# 4-voice_1_1.net
KiCad netlist of a schematic drawn in EAGLE
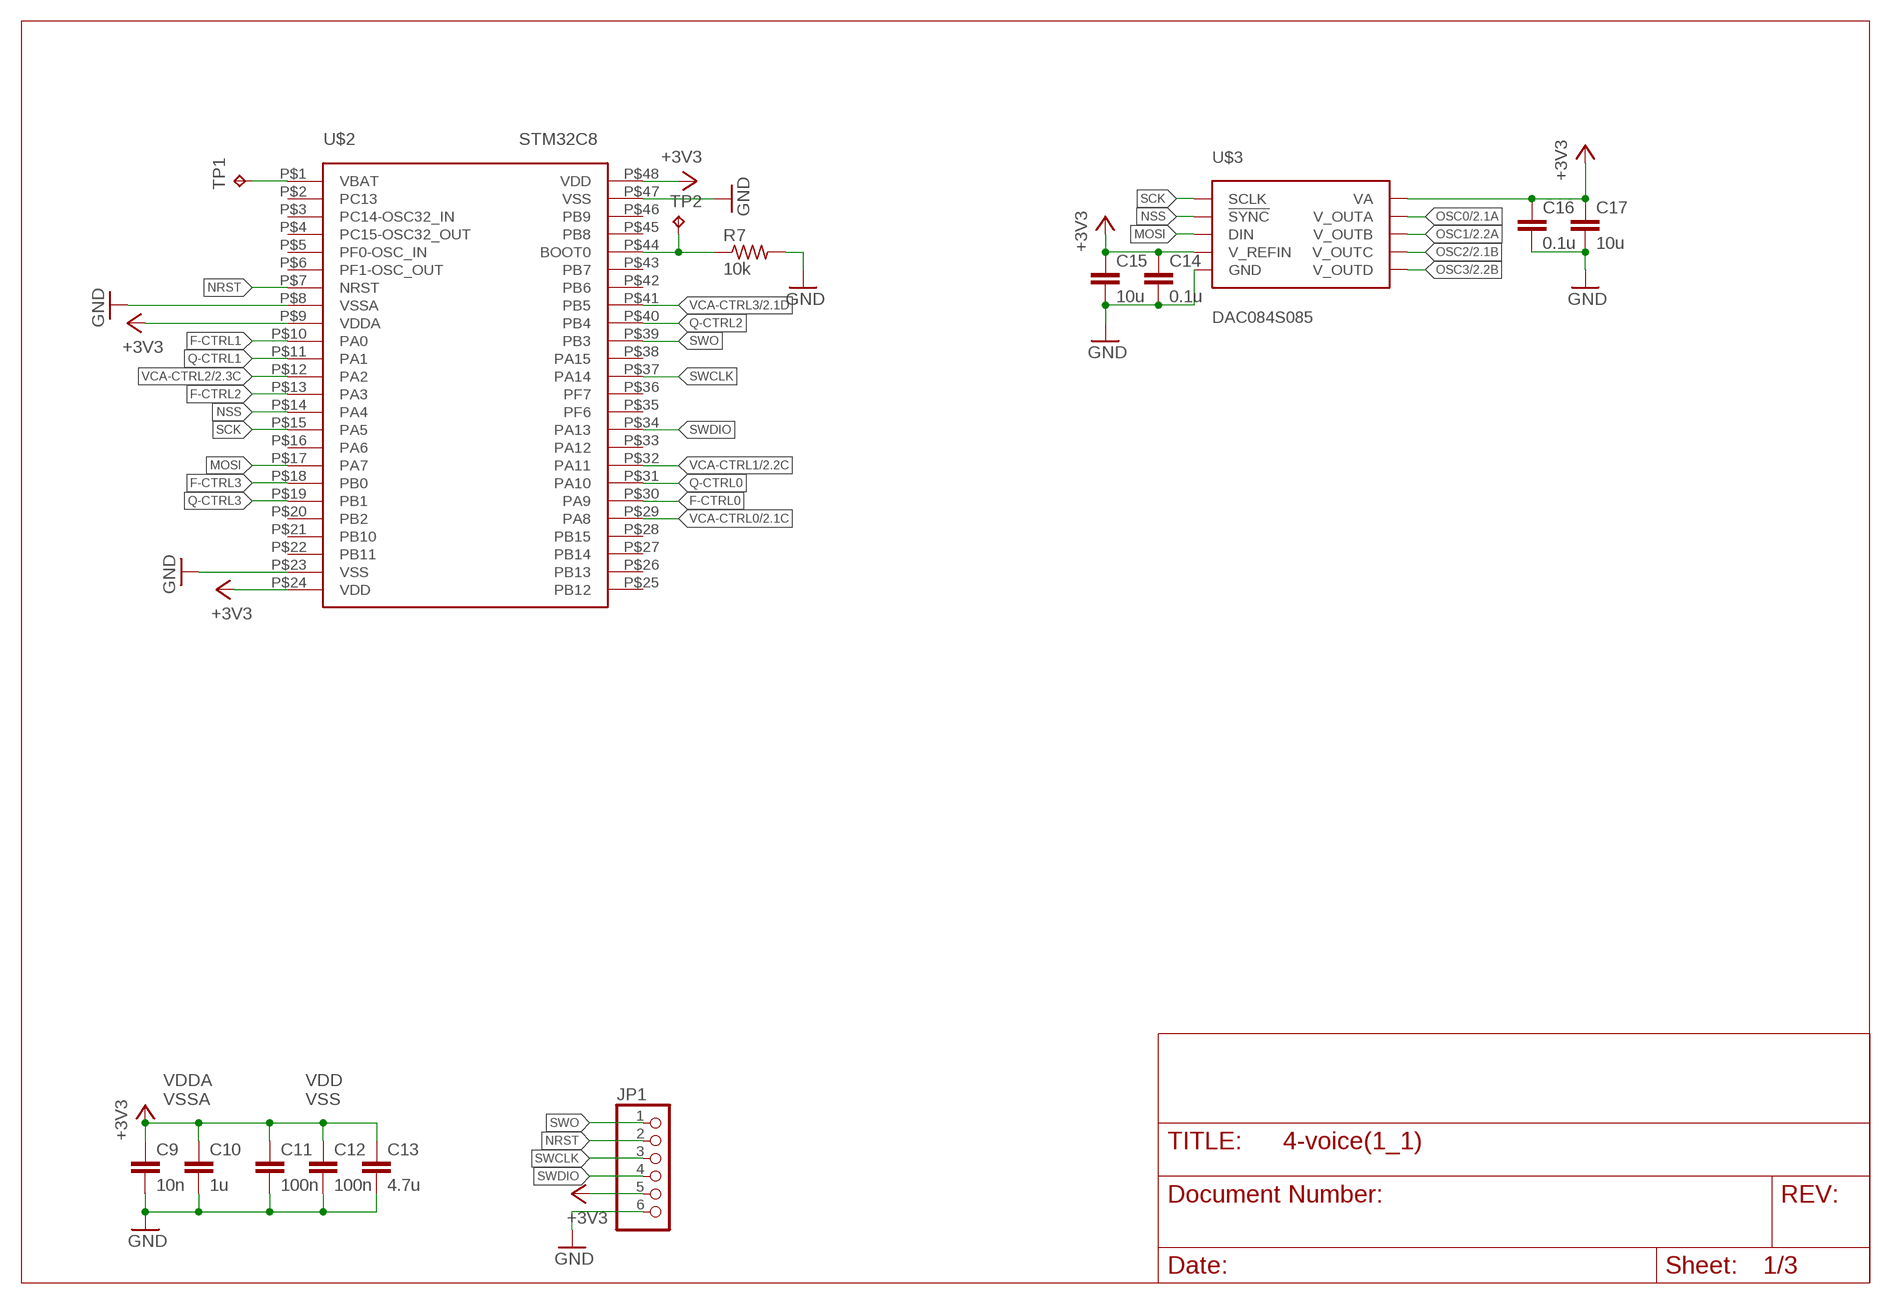
[diagram p0: schematic, sheet 1]
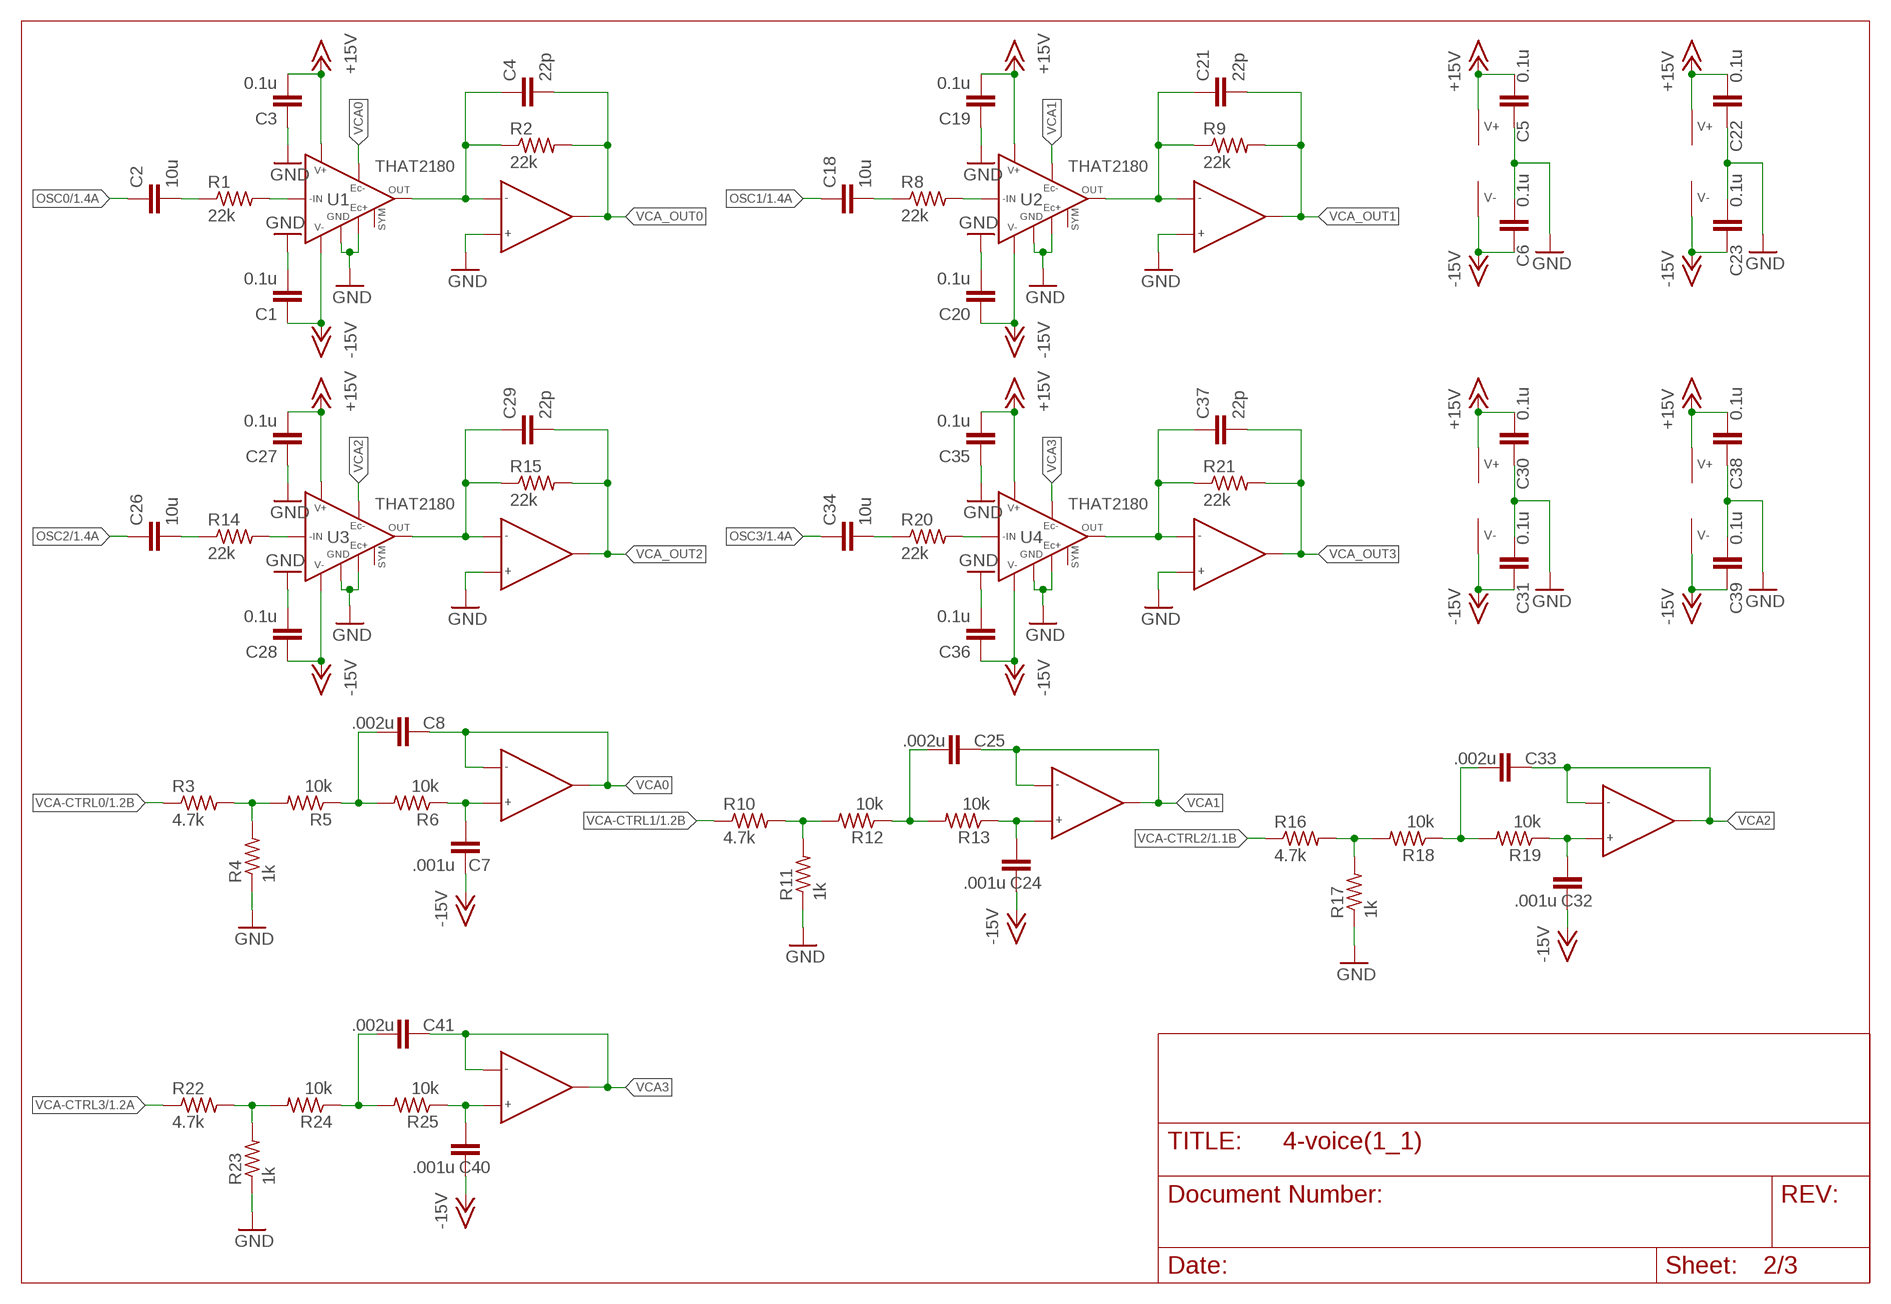
[diagram p1: schematic, sheet 2]
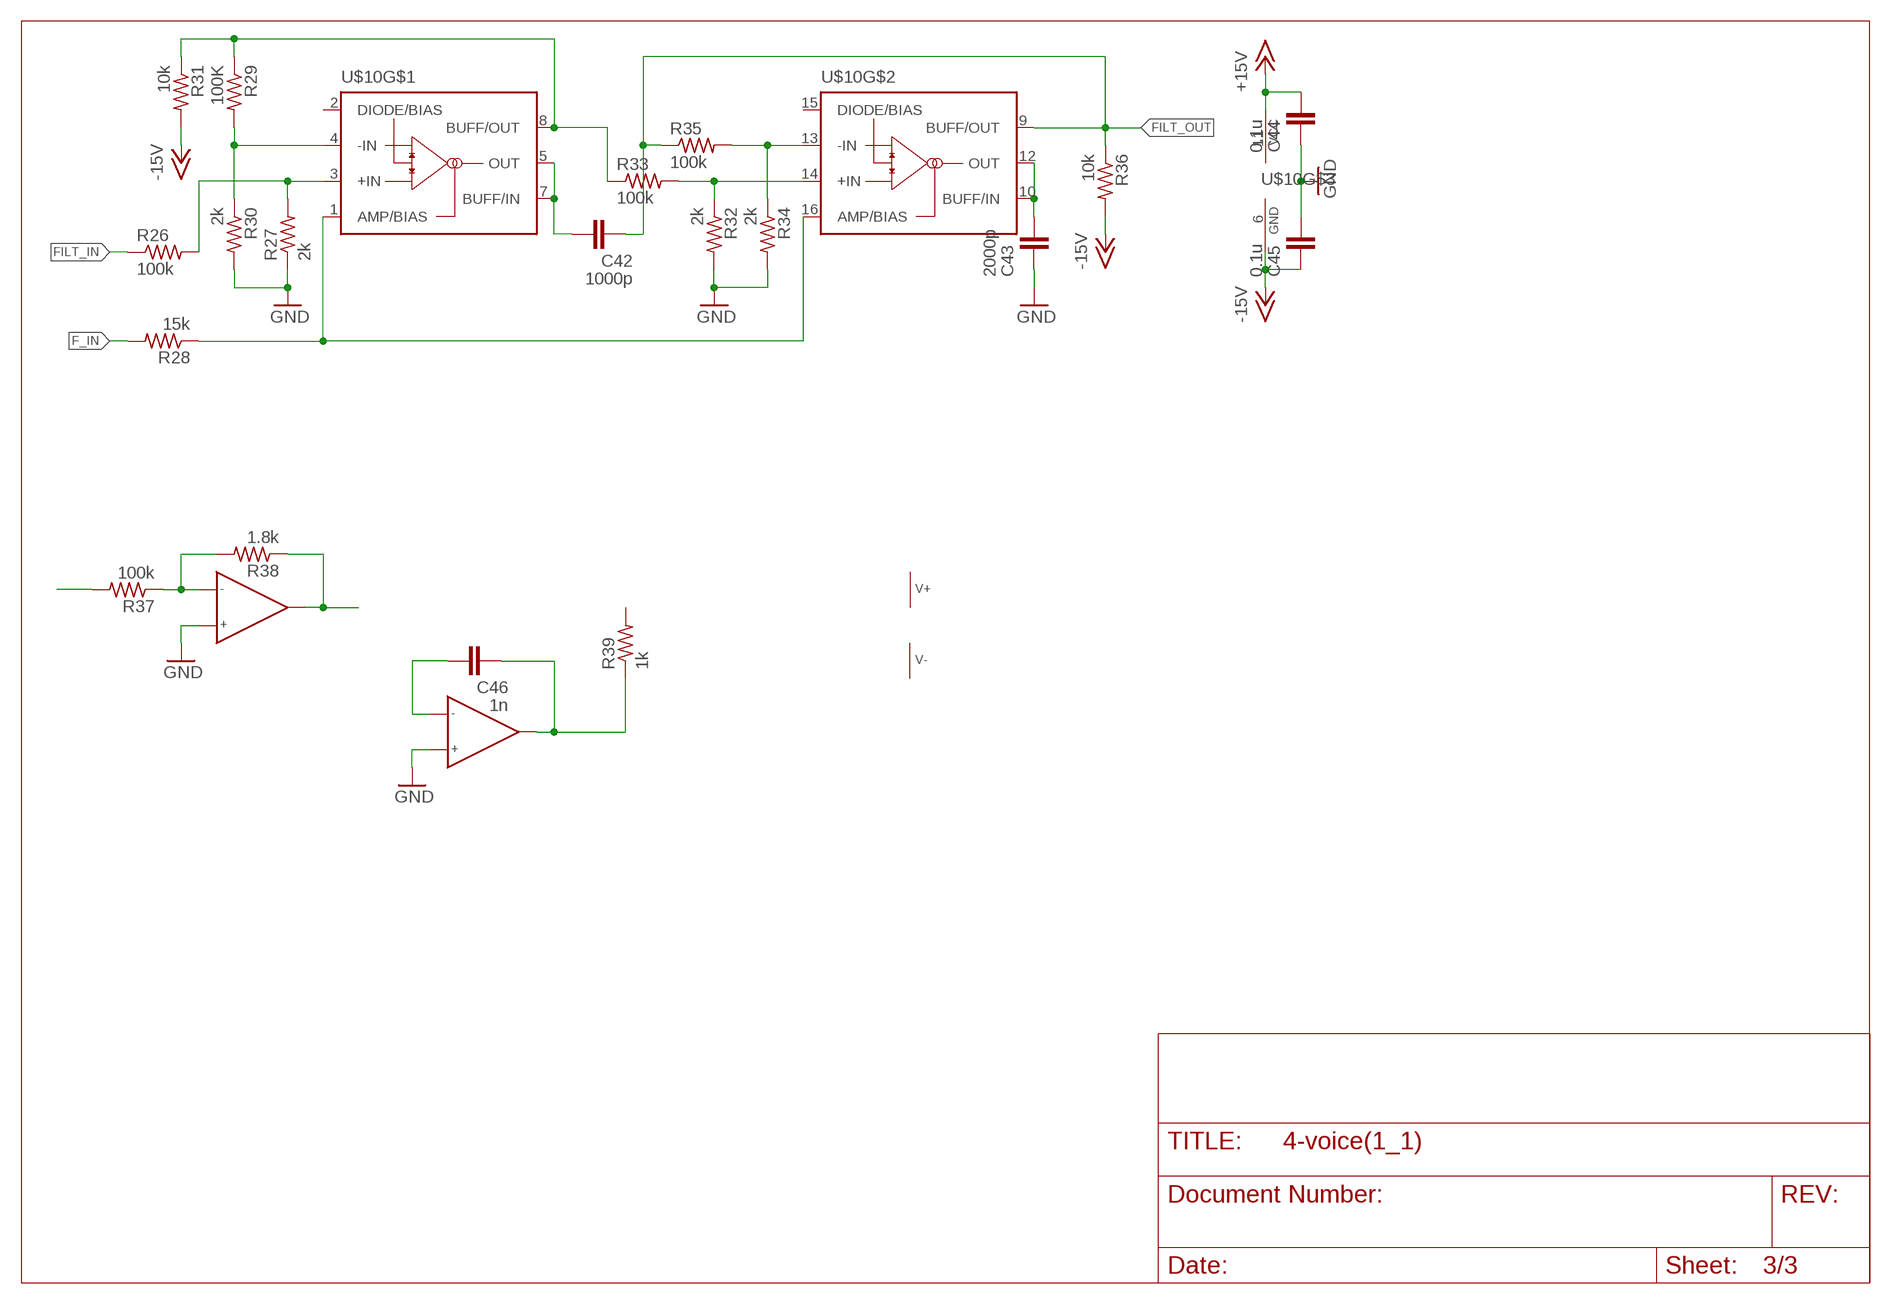
[diagram p2: schematic, sheet 3]

(export (version "E")
  (design (tool "Eeschema 10.0.6"))
  (components
    (comp (ref "C42")
      (value "1000p")
      (footprint "eagle-import:C1206")
      (libsource (lib "eagle-import") (part "resistor_348_C-EUC1206"))
    )
    (comp (ref "C43")
      (value "2000p")
      (footprint "eagle-import:C1206")
      (libsource (lib "eagle-import") (part "resistor_348_C-EUC1206"))
    )
    (comp (ref "C44")
      (value "0.1u")
      (footprint "eagle-import:C1206")
      (libsource (lib "eagle-import") (part "resistor_348_C-EUC1206"))
    )
    (comp (ref "C45")
      (value "0.1u")
      (footprint "eagle-import:C1206")
      (libsource (lib "eagle-import") (part "resistor_348_C-EUC1206"))
    )
    (comp (ref "C46")
      (value "1n")
      (footprint "eagle-import:C1206")
      (libsource (lib "eagle-import") (part "resistor_348_C-EUC1206"))
    )
    (comp (ref "R26")
      (value "100k")
      (footprint "eagle-import:R1206")
      (libsource (lib "eagle-import") (part "resistor_348_R-US_R1206"))
    )
    (comp (ref "R27")
      (value "2k")
      (footprint "eagle-import:R1206")
      (libsource (lib "eagle-import") (part "resistor_348_R-US_R1206"))
    )
    (comp (ref "R28")
      (value "15k")
      (footprint "eagle-import:R1206")
      (libsource (lib "eagle-import") (part "resistor_348_R-US_R1206"))
    )
    (comp (ref "R29")
      (value "100K")
      (footprint "eagle-import:R1206")
      (libsource (lib "eagle-import") (part "resistor_348_R-US_R1206"))
    )
    (comp (ref "R30")
      (value "2k")
      (footprint "eagle-import:R1206")
      (libsource (lib "eagle-import") (part "resistor_348_R-US_R1206"))
    )
    (comp (ref "R31")
      (value "10k")
      (footprint "eagle-import:R1206")
      (libsource (lib "eagle-import") (part "resistor_348_R-US_R1206"))
    )
    (comp (ref "R32")
      (value "2k")
      (footprint "eagle-import:R1206")
      (libsource (lib "eagle-import") (part "resistor_348_R-US_R1206"))
    )
    (comp (ref "R33")
      (value "100k")
      (footprint "eagle-import:R1206")
      (libsource (lib "eagle-import") (part "resistor_348_R-US_R1206"))
    )
    (comp (ref "R34")
      (value "2k")
      (footprint "eagle-import:R1206")
      (libsource (lib "eagle-import") (part "resistor_348_R-US_R1206"))
    )
    (comp (ref "R35")
      (value "100k")
      (footprint "eagle-import:R1206")
      (libsource (lib "eagle-import") (part "resistor_348_R-US_R1206"))
    )
    (comp (ref "R36")
      (value "10k")
      (footprint "eagle-import:R1206")
      (libsource (lib "eagle-import") (part "resistor_348_R-US_R1206"))
    )
    (comp (ref "R37")
      (value "100k")
      (footprint "eagle-import:R1206")
      (libsource (lib "eagle-import") (part "resistor_348_R-US_R1206"))
    )
    (comp (ref "R38")
      (value "1.8k")
      (footprint "eagle-import:R1206")
      (libsource (lib "eagle-import") (part "resistor_348_R-US_R1206"))
    )
    (comp (ref "R39")
      (value "1k")
      (footprint "eagle-import:R1206")
      (libsource (lib "eagle-import") (part "resistor_348_R-US_R1206"))
    )
    (comp (ref "U$10")
      (value "XX-13700DMP16")
      (footprint "eagle-import:DMP16")
      (libsource (lib "eagle-import") (part "XX-13700DMP16"))
    )
    (comp (ref "U$11")
      (value "TL072")
      (footprint "eagle-import:SOIC8")
      (libsource (lib "eagle-import") (part "TL072"))
    )
    (comp (ref "C1")
      (value "0.1u")
      (footprint "eagle-import:C1206")
      (libsource (lib "eagle-import") (part "C-EUC1206"))
    )
    (comp (ref "C2")
      (value "10u")
      (footprint "eagle-import:C1206")
      (libsource (lib "eagle-import") (part "C-EUC1206"))
    )
    (comp (ref "C3")
      (value "0.1u")
      (footprint "eagle-import:C1206")
      (libsource (lib "eagle-import") (part "C-EUC1206"))
    )
    (comp (ref "C4")
      (value "22p")
      (footprint "eagle-import:C1206")
      (libsource (lib "eagle-import") (part "C-EUC1206"))
    )
    (comp (ref "C5")
      (value "0.1u")
      (footprint "eagle-import:C1206")
      (libsource (lib "eagle-import") (part "C-EUC1206"))
    )
    (comp (ref "C6")
      (value "0.1u")
      (footprint "eagle-import:C1206")
      (libsource (lib "eagle-import") (part "C-EUC1206"))
    )
    (comp (ref "C7")
      (value ".001u")
      (footprint "eagle-import:C1206")
      (libsource (lib "eagle-import") (part "C-EUC1206"))
    )
    (comp (ref "C8")
      (value ".002u")
      (footprint "eagle-import:C1206")
      (libsource (lib "eagle-import") (part "C-EUC1206"))
    )
    (comp (ref "C18")
      (value "10u")
      (footprint "eagle-import:C1206")
      (libsource (lib "eagle-import") (part "C-EUC1206"))
    )
    (comp (ref "C19")
      (value "0.1u")
      (footprint "eagle-import:C1206")
      (libsource (lib "eagle-import") (part "C-EUC1206"))
    )
    (comp (ref "C20")
      (value "0.1u")
      (footprint "eagle-import:C1206")
      (libsource (lib "eagle-import") (part "C-EUC1206"))
    )
    (comp (ref "C21")
      (value "22p")
      (footprint "eagle-import:C1206")
      (libsource (lib "eagle-import") (part "C-EUC1206"))
    )
    (comp (ref "C22")
      (value "0.1u")
      (footprint "eagle-import:C1206")
      (libsource (lib "eagle-import") (part "C-EUC1206"))
    )
    (comp (ref "C23")
      (value "0.1u")
      (footprint "eagle-import:C1206")
      (libsource (lib "eagle-import") (part "C-EUC1206"))
    )
    (comp (ref "C24")
      (value ".001u")
      (footprint "eagle-import:C1206")
      (libsource (lib "eagle-import") (part "C-EUC1206"))
    )
    (comp (ref "C25")
      (value ".002u")
      (footprint "eagle-import:C1206")
      (libsource (lib "eagle-import") (part "C-EUC1206"))
    )
    (comp (ref "C26")
      (value "10u")
      (footprint "eagle-import:C1206")
      (libsource (lib "eagle-import") (part "C-EUC1206"))
    )
    (comp (ref "C27")
      (value "0.1u")
      (footprint "eagle-import:C1206")
      (libsource (lib "eagle-import") (part "C-EUC1206"))
    )
    (comp (ref "C28")
      (value "0.1u")
      (footprint "eagle-import:C1206")
      (libsource (lib "eagle-import") (part "C-EUC1206"))
    )
    (comp (ref "C29")
      (value "22p")
      (footprint "eagle-import:C1206")
      (libsource (lib "eagle-import") (part "C-EUC1206"))
    )
    (comp (ref "C30")
      (value "0.1u")
      (footprint "eagle-import:C1206")
      (libsource (lib "eagle-import") (part "C-EUC1206"))
    )
    (comp (ref "C31")
      (value "0.1u")
      (footprint "eagle-import:C1206")
      (libsource (lib "eagle-import") (part "C-EUC1206"))
    )
    (comp (ref "C32")
      (value ".001u")
      (footprint "eagle-import:C1206")
      (libsource (lib "eagle-import") (part "C-EUC1206"))
    )
    (comp (ref "C33")
      (value ".002u")
      (footprint "eagle-import:C1206")
      (libsource (lib "eagle-import") (part "C-EUC1206"))
    )
    (comp (ref "C34")
      (value "10u")
      (footprint "eagle-import:C1206")
      (libsource (lib "eagle-import") (part "C-EUC1206"))
    )
    (comp (ref "C35")
      (value "0.1u")
      (footprint "eagle-import:C1206")
      (libsource (lib "eagle-import") (part "C-EUC1206"))
    )
    (comp (ref "C36")
      (value "0.1u")
      (footprint "eagle-import:C1206")
      (libsource (lib "eagle-import") (part "C-EUC1206"))
    )
    (comp (ref "C37")
      (value "22p")
      (footprint "eagle-import:C1206")
      (libsource (lib "eagle-import") (part "C-EUC1206"))
    )
    (comp (ref "C38")
      (value "0.1u")
      (footprint "eagle-import:C1206")
      (libsource (lib "eagle-import") (part "C-EUC1206"))
    )
    (comp (ref "C39")
      (value "0.1u")
      (footprint "eagle-import:C1206")
      (libsource (lib "eagle-import") (part "C-EUC1206"))
    )
    (comp (ref "C40")
      (value ".001u")
      (footprint "eagle-import:C1206")
      (libsource (lib "eagle-import") (part "C-EUC1206"))
    )
    (comp (ref "C41")
      (value ".002u")
      (footprint "eagle-import:C1206")
      (libsource (lib "eagle-import") (part "C-EUC1206"))
    )
    (comp (ref "R1")
      (value "22k")
      (footprint "eagle-import:R1206")
      (libsource (lib "eagle-import") (part "R-US_R1206"))
    )
    (comp (ref "R2")
      (value "22k")
      (footprint "eagle-import:R1206")
      (libsource (lib "eagle-import") (part "R-US_R1206"))
    )
    (comp (ref "R3")
      (value "4.7k")
      (footprint "eagle-import:R1206")
      (libsource (lib "eagle-import") (part "R-US_R1206"))
    )
    (comp (ref "R4")
      (value "1k")
      (footprint "eagle-import:R1206")
      (libsource (lib "eagle-import") (part "R-US_R1206"))
    )
    (comp (ref "R5")
      (value "10k")
      (footprint "eagle-import:R1206")
      (libsource (lib "eagle-import") (part "R-US_R1206"))
    )
    (comp (ref "R6")
      (value "10k")
      (footprint "eagle-import:R1206")
      (libsource (lib "eagle-import") (part "R-US_R1206"))
    )
    (comp (ref "R8")
      (value "22k")
      (footprint "eagle-import:R1206")
      (libsource (lib "eagle-import") (part "R-US_R1206"))
    )
    (comp (ref "R9")
      (value "22k")
      (footprint "eagle-import:R1206")
      (libsource (lib "eagle-import") (part "R-US_R1206"))
    )
    (comp (ref "R10")
      (value "4.7k")
      (footprint "eagle-import:R1206")
      (libsource (lib "eagle-import") (part "R-US_R1206"))
    )
    (comp (ref "R11")
      (value "1k")
      (footprint "eagle-import:R1206")
      (libsource (lib "eagle-import") (part "R-US_R1206"))
    )
    (comp (ref "R12")
      (value "10k")
      (footprint "eagle-import:R1206")
      (libsource (lib "eagle-import") (part "R-US_R1206"))
    )
    (comp (ref "R13")
      (value "10k")
      (footprint "eagle-import:R1206")
      (libsource (lib "eagle-import") (part "R-US_R1206"))
    )
    (comp (ref "R14")
      (value "22k")
      (footprint "eagle-import:R1206")
      (libsource (lib "eagle-import") (part "R-US_R1206"))
    )
    (comp (ref "R15")
      (value "22k")
      (footprint "eagle-import:R1206")
      (libsource (lib "eagle-import") (part "R-US_R1206"))
    )
    (comp (ref "R16")
      (value "4.7k")
      (footprint "eagle-import:R1206")
      (libsource (lib "eagle-import") (part "R-US_R1206"))
    )
    (comp (ref "R17")
      (value "1k")
      (footprint "eagle-import:R1206")
      (libsource (lib "eagle-import") (part "R-US_R1206"))
    )
    (comp (ref "R18")
      (value "10k")
      (footprint "eagle-import:R1206")
      (libsource (lib "eagle-import") (part "R-US_R1206"))
    )
    (comp (ref "R19")
      (value "10k")
      (footprint "eagle-import:R1206")
      (libsource (lib "eagle-import") (part "R-US_R1206"))
    )
    (comp (ref "R20")
      (value "22k")
      (footprint "eagle-import:R1206")
      (libsource (lib "eagle-import") (part "R-US_R1206"))
    )
    (comp (ref "R21")
      (value "22k")
      (footprint "eagle-import:R1206")
      (libsource (lib "eagle-import") (part "R-US_R1206"))
    )
    (comp (ref "R22")
      (value "4.7k")
      (footprint "eagle-import:R1206")
      (libsource (lib "eagle-import") (part "R-US_R1206"))
    )
    (comp (ref "R23")
      (value "1k")
      (footprint "eagle-import:R1206")
      (libsource (lib "eagle-import") (part "R-US_R1206"))
    )
    (comp (ref "R24")
      (value "10k")
      (footprint "eagle-import:R1206")
      (libsource (lib "eagle-import") (part "R-US_R1206"))
    )
    (comp (ref "R25")
      (value "10k")
      (footprint "eagle-import:R1206")
      (libsource (lib "eagle-import") (part "R-US_R1206"))
    )
    (comp (ref "U$1")
      (value "TL072")
      (footprint "eagle-import:SOIC8")
      (libsource (lib "eagle-import") (part "TL072"))
    )
    (comp (ref "U$4")
      (value "TL072")
      (footprint "eagle-import:SOIC8")
      (fields (field (name "SPICEPREFIX") "J"))
      (libsource (lib "eagle-import") (part "TL072"))
    )
    (comp (ref "U$5")
      (value "TL072")
      (footprint "eagle-import:SOIC8")
      (libsource (lib "eagle-import") (part "TL072"))
    )
    (comp (ref "U$6")
      (value "TL072")
      (footprint "eagle-import:SOIC8")
      (fields (field (name "SPICEPREFIX") "B"))
      (libsource (lib "eagle-import") (part "TL072"))
    )
    (comp (ref "U$7")
      (value "TL072")
      (footprint "eagle-import:SOIC8")
      (libsource (lib "eagle-import") (part "TL072"))
    )
    (comp (ref "U$8")
      (value "TL072")
      (footprint "eagle-import:SOIC8")
      (fields (field (name "SPICEPREFIX") "B"))
      (libsource (lib "eagle-import") (part "TL072"))
    )
    (comp (ref "U$9")
      (value "TL072")
      (footprint "eagle-import:SOIC8")
      (fields (field (name "SPICEPREFIX") "B"))
      (libsource (lib "eagle-import") (part "TL072"))
    )
    (comp (ref "U1")
      (value "THAT2180")
      (footprint "eagle-import:SIP8")
      (libsource (lib "eagle-import") (part "THAT2180"))
    )
    (comp (ref "U2")
      (value "THAT2180")
      (footprint "eagle-import:SIP8")
      (libsource (lib "eagle-import") (part "THAT2180"))
    )
    (comp (ref "U3")
      (value "THAT2180")
      (footprint "eagle-import:SIP8")
      (libsource (lib "eagle-import") (part "THAT2180"))
    )
    (comp (ref "U4")
      (value "THAT2180")
      (footprint "eagle-import:SIP8")
      (libsource (lib "eagle-import") (part "THAT2180"))
    )
    (comp (ref "C9")
      (value "10n")
      (footprint "eagle-import:C1206")
      (libsource (lib "eagle-import") (part "C-EUC1206"))
    )
    (comp (ref "C10")
      (value "1u")
      (footprint "eagle-import:C1206")
      (libsource (lib "eagle-import") (part "C-EUC1206"))
    )
    (comp (ref "C11")
      (value "100n")
      (footprint "eagle-import:C1206")
      (libsource (lib "eagle-import") (part "C-EUC1206"))
    )
    (comp (ref "C12")
      (value "100n")
      (footprint "eagle-import:C1206")
      (libsource (lib "eagle-import") (part "C-EUC1206"))
    )
    (comp (ref "C13")
      (value "4.7u")
      (footprint "eagle-import:C1206")
      (libsource (lib "eagle-import") (part "C-EUC1206"))
    )
    (comp (ref "C14")
      (value "0.1u")
      (footprint "eagle-import:C1206")
      (libsource (lib "eagle-import") (part "C-EUC1206"))
    )
    (comp (ref "C15")
      (value "10u")
      (footprint "eagle-import:C1206")
      (libsource (lib "eagle-import") (part "C-EUC1206"))
    )
    (comp (ref "C16")
      (value "0.1u")
      (footprint "eagle-import:C1206")
      (libsource (lib "eagle-import") (part "C-EUC1206"))
    )
    (comp (ref "C17")
      (value "10u")
      (footprint "eagle-import:C1206")
      (libsource (lib "eagle-import") (part "C-EUC1206"))
    )
    (comp (ref "JP1")
      (value "PINHD-1X6")
      (footprint "eagle-import:1X06")
      (libsource (lib "eagle-import") (part "PINHD-1X6"))
    )
    (comp (ref "R7")
      (value "10k")
      (footprint "eagle-import:R1206")
      (libsource (lib "eagle-import") (part "R-US_R1206"))
    )
    (comp (ref "TP1")
      (value "TPPAD1-13")
      (footprint "eagle-import:P1-13")
      (libsource (lib "eagle-import") (part "TPPAD1-13"))
    )
    (comp (ref "TP2")
      (value "TPPAD1-13")
      (footprint "eagle-import:P1-13")
      (libsource (lib "eagle-import") (part "TPPAD1-13"))
    )
    (comp (ref "U$2")
      (value "STM32C8")
      (footprint "eagle-import:LQFP48")
      (libsource (lib "eagle-import") (part "STM32C8"))
    )
    (comp (ref "U$3")
      (value "DAC084S085")
      (footprint "eagle-import:VSSOP10")
      (libsource (lib "eagle-import") (part "DAC084S085"))
    )
  )
  (nets
    (net (code "1") (name "+3V3") (class "Default")
      (node (ref "C10") (pin "1") (pinfunction "1_1") (pintype "passive"))
      (node (ref "C11") (pin "1") (pinfunction "1_1") (pintype "passive"))
      (node (ref "C12") (pin "1") (pinfunction "1_1") (pintype "passive"))
      (node (ref "C13") (pin "1") (pinfunction "1_1") (pintype "passive"))
      (node (ref "C14") (pin "1") (pinfunction "1_1") (pintype "passive"))
      (node (ref "C15") (pin "1") (pinfunction "1_1") (pintype "passive"))
      (node (ref "C16") (pin "1") (pinfunction "1_1") (pintype "passive"))
      (node (ref "C17") (pin "1") (pinfunction "1_1") (pintype "passive"))
      (node (ref "C9") (pin "1") (pinfunction "1_1") (pintype "passive"))
      (node (ref "JP1") (pin "5") (pinfunction "5_5") (pintype "passive"))
      (node (ref "U$2") (pin "P$24") (pinfunction "VDD_P$24") (pintype "bidirectional"))
      (node (ref "U$2") (pin "P$48") (pinfunction "VDD_P$48") (pintype "bidirectional"))
      (node (ref "U$2") (pin "P$9") (pinfunction "VDDA_P$9") (pintype "bidirectional"))
      (node (ref "U$3") (pin "P$1") (pinfunction "VA_P$1") (pintype "bidirectional"))
      (node (ref "U$3") (pin "P$7") (pinfunction "V_REFIN_P$7") (pintype "bidirectional"))
    )
    (net (code "2") (name "+15V") (class "Default")
      (node (ref "C19") (pin "2") (pinfunction "2_2") (pintype "passive"))
      (node (ref "C22") (pin "2") (pinfunction "2_2") (pintype "passive"))
      (node (ref "C27") (pin "2") (pinfunction "2_2") (pintype "passive"))
      (node (ref "C3") (pin "2") (pinfunction "2_2") (pintype "passive"))
      (node (ref "C30") (pin "2") (pinfunction "2_2") (pintype "passive"))
      (node (ref "C35") (pin "2") (pinfunction "2_2") (pintype "passive"))
      (node (ref "C38") (pin "2") (pinfunction "2_2") (pintype "passive"))
      (node (ref "C44") (pin "1") (pinfunction "1_1") (pintype "passive"))
      (node (ref "C5") (pin "2") (pinfunction "2_2") (pintype "passive"))
      (node (ref "U$1") (pin "P$8") (pinfunction "V+_P$8") (pintype "bidirectional"))
      (node (ref "U$10") (pin "11") (pinfunction "VCC_11") (pintype "power_in"))
      (node (ref "U$4") (pin "P$8") (pinfunction "V+_P$8") (pintype "bidirectional"))
      (node (ref "U$6") (pin "P$8") (pinfunction "V+_P$8") (pintype "bidirectional"))
      (node (ref "U$8") (pin "P$8") (pinfunction "V+_P$8") (pintype "bidirectional"))
      (node (ref "U1") (pin "$P7") (pinfunction "V+_$P7") (pintype "bidirectional"))
      (node (ref "U2") (pin "$P7") (pinfunction "V+_$P7") (pintype "bidirectional"))
      (node (ref "U3") (pin "$P7") (pinfunction "V+_$P7") (pintype "bidirectional"))
      (node (ref "U4") (pin "$P7") (pinfunction "V+_$P7") (pintype "bidirectional"))
    )
    (net (code "3") (name "-15V") (class "Default")
      (node (ref "C1") (pin "1") (pinfunction "1_1") (pintype "passive"))
      (node (ref "C20") (pin "1") (pinfunction "1_1") (pintype "passive"))
      (node (ref "C23") (pin "1") (pinfunction "1_1") (pintype "passive"))
      (node (ref "C24") (pin "1") (pinfunction "1_1") (pintype "passive"))
      (node (ref "C28") (pin "1") (pinfunction "1_1") (pintype "passive"))
      (node (ref "C31") (pin "1") (pinfunction "1_1") (pintype "passive"))
      (node (ref "C32") (pin "1") (pinfunction "1_1") (pintype "passive"))
      (node (ref "C36") (pin "1") (pinfunction "1_1") (pintype "passive"))
      (node (ref "C39") (pin "1") (pinfunction "1_1") (pintype "passive"))
      (node (ref "C40") (pin "1") (pinfunction "1_1") (pintype "passive"))
      (node (ref "C45") (pin "2") (pinfunction "2_2") (pintype "passive"))
      (node (ref "C6") (pin "1") (pinfunction "1_1") (pintype "passive"))
      (node (ref "C7") (pin "1") (pinfunction "1_1") (pintype "passive"))
      (node (ref "R31") (pin "2") (pinfunction "2_2") (pintype "passive"))
      (node (ref "R36") (pin "2") (pinfunction "2_2") (pintype "passive"))
      (node (ref "U$1") (pin "P$4") (pinfunction "V-_P$4") (pintype "bidirectional"))
      (node (ref "U$10") (pin "6") (pinfunction "GND_6") (pintype "power_in"))
      (node (ref "U$4") (pin "P$4") (pinfunction "V-_P$4") (pintype "bidirectional"))
      (node (ref "U$6") (pin "P$4") (pinfunction "V-_P$4") (pintype "bidirectional"))
      (node (ref "U$8") (pin "P$4") (pinfunction "V-_P$4") (pintype "bidirectional"))
      (node (ref "U1") (pin "$P5") (pinfunction "V-_$P5") (pintype "bidirectional"))
      (node (ref "U2") (pin "$P5") (pinfunction "V-_$P5") (pintype "bidirectional"))
      (node (ref "U3") (pin "$P5") (pinfunction "V-_$P5") (pintype "bidirectional"))
      (node (ref "U4") (pin "$P5") (pinfunction "V-_$P5") (pintype "bidirectional"))
    )
    (net (code "4") (name "F-CTRL0") (class "Default")
      (node (ref "U$2") (pin "P$30") (pinfunction "PA9_P$30") (pintype "bidirectional"))
    )
    (net (code "5") (name "F-CTRL1") (class "Default")
      (node (ref "U$2") (pin "P$10") (pinfunction "PA0_P$10") (pintype "bidirectional"))
    )
    (net (code "6") (name "F-CTRL2") (class "Default")
      (node (ref "U$2") (pin "P$13") (pinfunction "PA3_P$13") (pintype "bidirectional"))
    )
    (net (code "7") (name "F-CTRL3") (class "Default")
      (node (ref "U$2") (pin "P$18") (pinfunction "PB0_P$18") (pintype "bidirectional"))
    )
    (net (code "8") (name "FILT_IN") (class "Default")
      (node (ref "R26") (pin "1") (pinfunction "1_1") (pintype "passive"))
    )
    (net (code "9") (name "FILT_OUT") (class "Default")
      (node (ref "C42") (pin "2") (pinfunction "2_2") (pintype "passive"))
      (node (ref "R35") (pin "1") (pinfunction "1_1") (pintype "passive"))
      (node (ref "R36") (pin "1") (pinfunction "1_1") (pintype "passive"))
      (node (ref "U$10") (pin "9") (pinfunction "BUFF/OUT_9") (pintype "output"))
    )
    (net (code "10") (name "F_IN") (class "Default")
      (node (ref "R28") (pin "2") (pinfunction "2_2") (pintype "passive"))
    )
    (net (code "11") (name "GND") (class "Default")
      (node (ref "C1") (pin "2") (pinfunction "2_2") (pintype "passive"))
      (node (ref "C10") (pin "2") (pinfunction "2_2") (pintype "passive"))
      (node (ref "C11") (pin "2") (pinfunction "2_2") (pintype "passive"))
      (node (ref "C12") (pin "2") (pinfunction "2_2") (pintype "passive"))
      (node (ref "C13") (pin "2") (pinfunction "2_2") (pintype "passive"))
      (node (ref "C14") (pin "2") (pinfunction "2_2") (pintype "passive"))
      (node (ref "C15") (pin "2") (pinfunction "2_2") (pintype "passive"))
      (node (ref "C16") (pin "2") (pinfunction "2_2") (pintype "passive"))
      (node (ref "C17") (pin "2") (pinfunction "2_2") (pintype "passive"))
      (node (ref "C19") (pin "1") (pinfunction "1_1") (pintype "passive"))
      (node (ref "C20") (pin "2") (pinfunction "2_2") (pintype "passive"))
      (node (ref "C22") (pin "1") (pinfunction "1_1") (pintype "passive"))
      (node (ref "C23") (pin "2") (pinfunction "2_2") (pintype "passive"))
      (node (ref "C27") (pin "1") (pinfunction "1_1") (pintype "passive"))
      (node (ref "C28") (pin "2") (pinfunction "2_2") (pintype "passive"))
      (node (ref "C3") (pin "1") (pinfunction "1_1") (pintype "passive"))
      (node (ref "C30") (pin "1") (pinfunction "1_1") (pintype "passive"))
      (node (ref "C31") (pin "2") (pinfunction "2_2") (pintype "passive"))
      (node (ref "C35") (pin "1") (pinfunction "1_1") (pintype "passive"))
      (node (ref "C36") (pin "2") (pinfunction "2_2") (pintype "passive"))
      (node (ref "C38") (pin "1") (pinfunction "1_1") (pintype "passive"))
      (node (ref "C39") (pin "2") (pinfunction "2_2") (pintype "passive"))
      (node (ref "C43") (pin "2") (pinfunction "2_2") (pintype "passive"))
      (node (ref "C44") (pin "2") (pinfunction "2_2") (pintype "passive"))
      (node (ref "C45") (pin "1") (pinfunction "1_1") (pintype "passive"))
      (node (ref "C5") (pin "1") (pinfunction "1_1") (pintype "passive"))
      (node (ref "C6") (pin "2") (pinfunction "2_2") (pintype "passive"))
      (node (ref "C9") (pin "2") (pinfunction "2_2") (pintype "passive"))
      (node (ref "JP1") (pin "6") (pinfunction "6_6") (pintype "passive"))
      (node (ref "R11") (pin "1") (pinfunction "1_1") (pintype "passive"))
      (node (ref "R17") (pin "1") (pinfunction "1_1") (pintype "passive"))
      (node (ref "R23") (pin "1") (pinfunction "1_1") (pintype "passive"))
      (node (ref "R27") (pin "1") (pinfunction "1_1") (pintype "passive"))
      (node (ref "R30") (pin "2") (pinfunction "2_2") (pintype "passive"))
      (node (ref "R32") (pin "2") (pinfunction "2_2") (pintype "passive"))
      (node (ref "R34") (pin "2") (pinfunction "2_2") (pintype "passive"))
      (node (ref "R4") (pin "1") (pinfunction "1_1") (pintype "passive"))
      (node (ref "R7") (pin "2") (pinfunction "2_2") (pintype "passive"))
      (node (ref "U$1") (pin "P$3") (pinfunction "IN+_P$3") (pintype "bidirectional"))
      (node (ref "U$11") (pin "P$3") (pinfunction "IN+_P$3") (pintype "bidirectional"))
      (node (ref "U$11") (pin "P$5") (pinfunction "IN+_P$5") (pintype "bidirectional"))
      (node (ref "U$2") (pin "P$23") (pinfunction "VSS_P$23") (pintype "bidirectional"))
      (node (ref "U$2") (pin "P$47") (pinfunction "VSS_P$47") (pintype "bidirectional"))
      (node (ref "U$2") (pin "P$8") (pinfunction "VSSA_P$8") (pintype "bidirectional"))
      (node (ref "U$3") (pin "P$6") (pinfunction "GND_P$6") (pintype "bidirectional"))
      (node (ref "U$4") (pin "P$3") (pinfunction "IN+_P$3") (pintype "bidirectional"))
      (node (ref "U$5") (pin "P$3") (pinfunction "IN+_P$3") (pintype "bidirectional"))
      (node (ref "U$7") (pin "P$3") (pinfunction "IN+_P$3") (pintype "bidirectional"))
      (node (ref "U1") (pin "$P2") (pinfunction "EC+_$P2") (pintype "bidirectional"))
      (node (ref "U1") (pin "$P6") (pinfunction "GND_$P6") (pintype "bidirectional"))
      (node (ref "U2") (pin "$P2") (pinfunction "EC+_$P2") (pintype "bidirectional"))
      (node (ref "U2") (pin "$P6") (pinfunction "GND_$P6") (pintype "bidirectional"))
      (node (ref "U3") (pin "$P2") (pinfunction "EC+_$P2") (pintype "bidirectional"))
      (node (ref "U3") (pin "$P6") (pinfunction "GND_$P6") (pintype "bidirectional"))
      (node (ref "U4") (pin "$P2") (pinfunction "EC+_$P2") (pintype "bidirectional"))
      (node (ref "U4") (pin "$P6") (pinfunction "GND_$P6") (pintype "bidirectional"))
    )
    (net (code "12") (name "MOSI") (class "Default")
      (node (ref "U$2") (pin "P$17") (pinfunction "PA7_P$17") (pintype "bidirectional"))
      (node (ref "U$3") (pin "P$8") (pinfunction "DIN_P$8") (pintype "bidirectional"))
    )
    (net (code "13") (name "NRST") (class "Default")
      (node (ref "JP1") (pin "2") (pinfunction "2_2") (pintype "passive"))
      (node (ref "U$2") (pin "P$7") (pinfunction "NRST_P$7") (pintype "bidirectional"))
    )
    (net (code "14") (name "NSS") (class "Default")
      (node (ref "U$2") (pin "P$14") (pinfunction "PA4_P$14") (pintype "bidirectional"))
      (node (ref "U$3") (pin "P$9") (pinfunction "~{SYNC}_P$9") (pintype "bidirectional"))
    )
    (net (code "15") (name "Net-(C2-Pad2)") (class "Default")
      (node (ref "C2") (pin "2") (pinfunction "2_2") (pintype "passive"))
      (node (ref "R1") (pin "1") (pinfunction "1_1") (pintype "passive"))
    )
    (net (code "16") (name "Net-(C8-Pad2)") (class "Default")
      (node (ref "C8") (pin "2") (pinfunction "2_2") (pintype "passive"))
      (node (ref "R5") (pin "1") (pinfunction "1_1") (pintype "passive"))
      (node (ref "R6") (pin "2") (pinfunction "2_2") (pintype "passive"))
    )
    (net (code "17") (name "Net-(C18-Pad2)") (class "Default")
      (node (ref "C18") (pin "2") (pinfunction "2_2") (pintype "passive"))
      (node (ref "R8") (pin "1") (pinfunction "1_1") (pintype "passive"))
    )
    (net (code "18") (name "Net-(C25-Pad2)") (class "Default")
      (node (ref "C25") (pin "2") (pinfunction "2_2") (pintype "passive"))
      (node (ref "R12") (pin "1") (pinfunction "1_1") (pintype "passive"))
      (node (ref "R13") (pin "2") (pinfunction "2_2") (pintype "passive"))
    )
    (net (code "19") (name "Net-(C26-Pad2)") (class "Default")
      (node (ref "C26") (pin "2") (pinfunction "2_2") (pintype "passive"))
      (node (ref "R14") (pin "1") (pinfunction "1_1") (pintype "passive"))
    )
    (net (code "20") (name "Net-(C33-Pad2)") (class "Default")
      (node (ref "C33") (pin "2") (pinfunction "2_2") (pintype "passive"))
      (node (ref "R18") (pin "1") (pinfunction "1_1") (pintype "passive"))
      (node (ref "R19") (pin "2") (pinfunction "2_2") (pintype "passive"))
    )
    (net (code "21") (name "Net-(C34-Pad2)") (class "Default")
      (node (ref "C34") (pin "2") (pinfunction "2_2") (pintype "passive"))
      (node (ref "R20") (pin "1") (pinfunction "1_1") (pintype "passive"))
    )
    (net (code "22") (name "Net-(C41-Pad2)") (class "Default")
      (node (ref "C41") (pin "2") (pinfunction "2_2") (pintype "passive"))
      (node (ref "R24") (pin "1") (pinfunction "1_1") (pintype "passive"))
      (node (ref "R25") (pin "2") (pinfunction "2_2") (pintype "passive"))
    )
    (net (code "23") (name "Net-(R3-Pad2)") (class "Default")
      (node (ref "R3") (pin "2") (pinfunction "2_2") (pintype "passive"))
      (node (ref "R4") (pin "2") (pinfunction "2_2") (pintype "passive"))
      (node (ref "R5") (pin "2") (pinfunction "2_2") (pintype "passive"))
    )
    (net (code "24") (name "Net-(R10-Pad2)") (class "Default")
      (node (ref "R10") (pin "2") (pinfunction "2_2") (pintype "passive"))
      (node (ref "R11") (pin "2") (pinfunction "2_2") (pintype "passive"))
      (node (ref "R12") (pin "2") (pinfunction "2_2") (pintype "passive"))
    )
    (net (code "25") (name "Net-(R16-Pad2)") (class "Default")
      (node (ref "R16") (pin "2") (pinfunction "2_2") (pintype "passive"))
      (node (ref "R17") (pin "2") (pinfunction "2_2") (pintype "passive"))
      (node (ref "R18") (pin "2") (pinfunction "2_2") (pintype "passive"))
    )
    (net (code "26") (name "Net-(R22-Pad2)") (class "Default")
      (node (ref "R22") (pin "2") (pinfunction "2_2") (pintype "passive"))
      (node (ref "R23") (pin "2") (pinfunction "2_2") (pintype "passive"))
      (node (ref "R24") (pin "2") (pinfunction "2_2") (pintype "passive"))
    )
    (net (code "27") (name "Net-(U$1A-IN-)") (class "Default")
      (node (ref "C4") (pin "1") (pinfunction "1_1") (pintype "passive"))
      (node (ref "R2") (pin "1") (pinfunction "1_1") (pintype "passive"))
      (node (ref "U$1") (pin "P$2") (pinfunction "IN-_P$2") (pintype "bidirectional"))
      (node (ref "U1") (pin "$P8") (pinfunction "OUT_$P8") (pintype "bidirectional"))
    )
    (net (code "28") (name "Net-(U$1B-IN+)") (class "Default")
      (node (ref "C7") (pin "2") (pinfunction "2_2") (pintype "passive"))
      (node (ref "R6") (pin "1") (pinfunction "1_1") (pintype "passive"))
      (node (ref "U$1") (pin "P$5") (pinfunction "IN+_P$5") (pintype "bidirectional"))
    )
    (net (code "29") (name "Net-(U$2-BOOT0)") (class "Default")
      (node (ref "R7") (pin "1") (pinfunction "1_1") (pintype "passive"))
      (node (ref "TP2") (pin "TP") (pinfunction "TP_TP") (pintype "input"))
      (node (ref "U$2") (pin "P$44") (pinfunction "BOOT0_P$44") (pintype "bidirectional"))
    )
    (net (code "30") (name "Net-(U$2-VBAT)") (class "Default")
      (node (ref "TP1") (pin "TP") (pinfunction "TP_TP") (pintype "input"))
      (node (ref "U$2") (pin "P$1") (pinfunction "VBAT_P$1") (pintype "bidirectional"))
    )
    (net (code "31") (name "Net-(U$4A-IN-)") (class "Default")
      (node (ref "C21") (pin "1") (pinfunction "1_1") (pintype "passive"))
      (node (ref "R9") (pin "1") (pinfunction "1_1") (pintype "passive"))
      (node (ref "U$4") (pin "P$2") (pinfunction "IN-_P$2") (pintype "bidirectional"))
      (node (ref "U2") (pin "$P8") (pinfunction "OUT_$P8") (pintype "bidirectional"))
    )
    (net (code "32") (name "Net-(U$4B-IN+)") (class "Default")
      (node (ref "C24") (pin "2") (pinfunction "2_2") (pintype "passive"))
      (node (ref "R13") (pin "1") (pinfunction "1_1") (pintype "passive"))
      (node (ref "U$4") (pin "P$5") (pinfunction "IN+_P$5") (pintype "bidirectional"))
    )
    (net (code "33") (name "Net-(U$5A-IN-)") (class "Default")
      (node (ref "C29") (pin "1") (pinfunction "1_1") (pintype "passive"))
      (node (ref "R15") (pin "1") (pinfunction "1_1") (pintype "passive"))
      (node (ref "U$5") (pin "P$2") (pinfunction "IN-_P$2") (pintype "bidirectional"))
      (node (ref "U3") (pin "$P8") (pinfunction "OUT_$P8") (pintype "bidirectional"))
    )
    (net (code "34") (name "Net-(U$6B-IN+)") (class "Default")
      (node (ref "C32") (pin "2") (pinfunction "2_2") (pintype "passive"))
      (node (ref "R19") (pin "1") (pinfunction "1_1") (pintype "passive"))
      (node (ref "U$6") (pin "P$5") (pinfunction "IN+_P$5") (pintype "bidirectional"))
    )
    (net (code "35") (name "Net-(U$7A-IN-)") (class "Default")
      (node (ref "C37") (pin "1") (pinfunction "1_1") (pintype "passive"))
      (node (ref "R21") (pin "1") (pinfunction "1_1") (pintype "passive"))
      (node (ref "U$7") (pin "P$2") (pinfunction "IN-_P$2") (pintype "bidirectional"))
      (node (ref "U4") (pin "$P8") (pinfunction "OUT_$P8") (pintype "bidirectional"))
    )
    (net (code "36") (name "Net-(U$9B-IN+)") (class "Default")
      (node (ref "C40") (pin "2") (pinfunction "2_2") (pintype "passive"))
      (node (ref "R25") (pin "1") (pinfunction "1_1") (pintype "passive"))
      (node (ref "U$9") (pin "P$5") (pinfunction "IN+_P$5") (pintype "bidirectional"))
    )
    (net (code "37") (name "Net-(U$10A-+IN)") (class "Default")
      (node (ref "R26") (pin "2") (pinfunction "2_2") (pintype "passive"))
      (node (ref "R27") (pin "2") (pinfunction "2_2") (pintype "passive"))
      (node (ref "U$10") (pin "3") (pinfunction "+IN_3") (pintype "input"))
    )
    (net (code "38") (name "Net-(U$10A--IN)") (class "Default")
      (node (ref "R29") (pin "2") (pinfunction "2_2") (pintype "passive"))
      (node (ref "R30") (pin "1") (pinfunction "1_1") (pintype "passive"))
      (node (ref "U$10") (pin "4") (pinfunction "-IN_4") (pintype "input"))
    )
    (net (code "39") (name "Net-(U$10A-AMP{slash}BIAS)") (class "Default")
      (node (ref "R28") (pin "1") (pinfunction "1_1") (pintype "passive"))
      (node (ref "U$10") (pin "1") (pinfunction "AMP/BIAS_1") (pintype "passive"))
      (node (ref "U$10") (pin "16") (pinfunction "AMP/BIAS_16") (pintype "passive"))
    )
    (net (code "40") (name "Net-(U$10A-BUFF{slash}IN)") (class "Default")
      (node (ref "C42") (pin "1") (pinfunction "1_1") (pintype "passive"))
      (node (ref "U$10") (pin "5") (pinfunction "OUT_5") (pintype "output"))
      (node (ref "U$10") (pin "7") (pinfunction "BUFF/IN_7") (pintype "input"))
    )
    (net (code "41") (name "Net-(U$10A-BUFF{slash}OUT)") (class "Default")
      (node (ref "R29") (pin "1") (pinfunction "1_1") (pintype "passive"))
      (node (ref "R31") (pin "1") (pinfunction "1_1") (pintype "passive"))
      (node (ref "R33") (pin "1") (pinfunction "1_1") (pintype "passive"))
      (node (ref "U$10") (pin "8") (pinfunction "BUFF/OUT_8") (pintype "output"))
    )
    (net (code "42") (name "Net-(U$10B-+IN)") (class "Default")
      (node (ref "R32") (pin "1") (pinfunction "1_1") (pintype "passive"))
      (node (ref "R33") (pin "2") (pinfunction "2_2") (pintype "passive"))
      (node (ref "U$10") (pin "14") (pinfunction "+IN_14") (pintype "input"))
    )
    (net (code "43") (name "Net-(U$10B--IN)") (class "Default")
      (node (ref "R34") (pin "1") (pinfunction "1_1") (pintype "passive"))
      (node (ref "R35") (pin "2") (pinfunction "2_2") (pintype "passive"))
      (node (ref "U$10") (pin "13") (pinfunction "-IN_13") (pintype "input"))
    )
    (net (code "44") (name "Net-(U$10B-BUFF{slash}IN)") (class "Default")
      (node (ref "C43") (pin "1") (pinfunction "1_1") (pintype "passive"))
      (node (ref "U$10") (pin "10") (pinfunction "BUFF/IN_10") (pintype "input"))
      (node (ref "U$10") (pin "12") (pinfunction "OUT_12") (pintype "output"))
    )
    (net (code "45") (name "Net-(U$11A-IN-)") (class "Default")
      (node (ref "R37") (pin "1") (pinfunction "1_1") (pintype "passive"))
      (node (ref "R38") (pin "2") (pinfunction "2_2") (pintype "passive"))
      (node (ref "U$11") (pin "P$2") (pinfunction "IN-_P$2") (pintype "bidirectional"))
    )
    (net (code "46") (name "Net-(U$11A-OUT)") (class "Default")
      (node (ref "R38") (pin "1") (pinfunction "1_1") (pintype "passive"))
      (node (ref "U$11") (pin "P$1") (pinfunction "OUT_P$1") (pintype "bidirectional"))
    )
    (net (code "47") (name "Net-(U$11B-IN-)") (class "Default")
      (node (ref "C46") (pin "1") (pinfunction "1_1") (pintype "passive"))
      (node (ref "U$11") (pin "P$6") (pinfunction "IN-_P$6") (pintype "bidirectional"))
    )
    (net (code "48") (name "Net-(U$11B-OUT)") (class "Default")
      (node (ref "C46") (pin "2") (pinfunction "2_2") (pintype "passive"))
      (node (ref "R39") (pin "1") (pinfunction "1_1") (pintype "passive"))
      (node (ref "U$11") (pin "P$7") (pinfunction "OUT_P$7") (pintype "bidirectional"))
    )
    (net (code "49") (name "Net-(U1--IN)") (class "Default")
      (node (ref "R1") (pin "2") (pinfunction "2_2") (pintype "passive"))
      (node (ref "U1") (pin "$P1") (pinfunction "-IN_$P1") (pintype "bidirectional"))
    )
    (net (code "50") (name "Net-(U2--IN)") (class "Default")
      (node (ref "R8") (pin "2") (pinfunction "2_2") (pintype "passive"))
      (node (ref "U2") (pin "$P1") (pinfunction "-IN_$P1") (pintype "bidirectional"))
    )
    (net (code "51") (name "Net-(U3--IN)") (class "Default")
      (node (ref "R14") (pin "2") (pinfunction "2_2") (pintype "passive"))
      (node (ref "U3") (pin "$P1") (pinfunction "-IN_$P1") (pintype "bidirectional"))
    )
    (net (code "52") (name "Net-(U4--IN)") (class "Default")
      (node (ref "R20") (pin "2") (pinfunction "2_2") (pintype "passive"))
      (node (ref "U4") (pin "$P1") (pinfunction "-IN_$P1") (pintype "bidirectional"))
    )
    (net (code "53") (name "OSC0") (class "Default")
      (node (ref "C2") (pin "1") (pinfunction "1_1") (pintype "passive"))
      (node (ref "U$3") (pin "P$2") (pinfunction "V_OUTA_P$2") (pintype "bidirectional"))
    )
    (net (code "54") (name "OSC1") (class "Default")
      (node (ref "C18") (pin "1") (pinfunction "1_1") (pintype "passive"))
      (node (ref "U$3") (pin "P$3") (pinfunction "V_OUTB_P$3") (pintype "bidirectional"))
    )
    (net (code "55") (name "OSC2") (class "Default")
      (node (ref "C26") (pin "1") (pinfunction "1_1") (pintype "passive"))
      (node (ref "U$3") (pin "P$4") (pinfunction "V_OUTC_P$4") (pintype "bidirectional"))
    )
    (net (code "56") (name "OSC3") (class "Default")
      (node (ref "C34") (pin "1") (pinfunction "1_1") (pintype "passive"))
      (node (ref "U$3") (pin "P$5") (pinfunction "V_OUTD_P$5") (pintype "bidirectional"))
    )
    (net (code "57") (name "Q-CTRL0") (class "Default")
      (node (ref "U$2") (pin "P$31") (pinfunction "PA10_P$31") (pintype "bidirectional"))
    )
    (net (code "58") (name "Q-CTRL1") (class "Default")
      (node (ref "U$2") (pin "P$11") (pinfunction "PA1_P$11") (pintype "bidirectional"))
    )
    (net (code "59") (name "Q-CTRL2") (class "Default")
      (node (ref "U$2") (pin "P$40") (pinfunction "PB4_P$40") (pintype "bidirectional"))
    )
    (net (code "60") (name "Q-CTRL3") (class "Default")
      (node (ref "U$2") (pin "P$19") (pinfunction "PB1_P$19") (pintype "bidirectional"))
    )
    (net (code "61") (name "SCK") (class "Default")
      (node (ref "U$2") (pin "P$15") (pinfunction "PA5_P$15") (pintype "bidirectional"))
      (node (ref "U$3") (pin "P$10") (pinfunction "SCLK_P$10") (pintype "bidirectional"))
    )
    (net (code "62") (name "SWCLK") (class "Default")
      (node (ref "JP1") (pin "3") (pinfunction "3_3") (pintype "passive"))
      (node (ref "U$2") (pin "P$37") (pinfunction "PA14_P$37") (pintype "bidirectional"))
    )
    (net (code "63") (name "SWDIO") (class "Default")
      (node (ref "JP1") (pin "4") (pinfunction "4_4") (pintype "passive"))
      (node (ref "U$2") (pin "P$34") (pinfunction "PA13_P$34") (pintype "bidirectional"))
    )
    (net (code "64") (name "SWO") (class "Default")
      (node (ref "JP1") (pin "1") (pinfunction "1_1") (pintype "passive"))
      (node (ref "U$2") (pin "P$39") (pinfunction "PB3_P$39") (pintype "bidirectional"))
    )
    (net (code "65") (name "VCA-CTRL0") (class "Default")
      (node (ref "R3") (pin "1") (pinfunction "1_1") (pintype "passive"))
      (node (ref "U$2") (pin "P$29") (pinfunction "PA8_P$29") (pintype "bidirectional"))
    )
    (net (code "66") (name "VCA-CTRL1") (class "Default")
      (node (ref "R10") (pin "1") (pinfunction "1_1") (pintype "passive"))
      (node (ref "U$2") (pin "P$32") (pinfunction "PA11_P$32") (pintype "bidirectional"))
    )
    (net (code "67") (name "VCA-CTRL2") (class "Default")
      (node (ref "R16") (pin "1") (pinfunction "1_1") (pintype "passive"))
      (node (ref "U$2") (pin "P$12") (pinfunction "PA2_P$12") (pintype "bidirectional"))
    )
    (net (code "68") (name "VCA-CTRL3") (class "Default")
      (node (ref "R22") (pin "1") (pinfunction "1_1") (pintype "passive"))
      (node (ref "U$2") (pin "P$41") (pinfunction "PB5_P$41") (pintype "bidirectional"))
    )
    (net (code "69") (name "VCA0") (class "Default")
      (node (ref "C8") (pin "1") (pinfunction "1_1") (pintype "passive"))
      (node (ref "U$1") (pin "P$6") (pinfunction "IN-_P$6") (pintype "bidirectional"))
      (node (ref "U$1") (pin "P$7") (pinfunction "OUT_P$7") (pintype "bidirectional"))
      (node (ref "U1") (pin "$P3") (pinfunction "EC-_$P3") (pintype "bidirectional"))
    )
    (net (code "70") (name "VCA1") (class "Default")
      (node (ref "C25") (pin "1") (pinfunction "1_1") (pintype "passive"))
      (node (ref "U$4") (pin "P$6") (pinfunction "IN-_P$6") (pintype "bidirectional"))
      (node (ref "U$4") (pin "P$7") (pinfunction "OUT_P$7") (pintype "bidirectional"))
      (node (ref "U2") (pin "$P3") (pinfunction "EC-_$P3") (pintype "bidirectional"))
    )
    (net (code "71") (name "VCA2") (class "Default")
      (node (ref "C33") (pin "1") (pinfunction "1_1") (pintype "passive"))
      (node (ref "U$6") (pin "P$6") (pinfunction "IN-_P$6") (pintype "bidirectional"))
      (node (ref "U$6") (pin "P$7") (pinfunction "OUT_P$7") (pintype "bidirectional"))
      (node (ref "U3") (pin "$P3") (pinfunction "EC-_$P3") (pintype "bidirectional"))
    )
    (net (code "72") (name "VCA3") (class "Default")
      (node (ref "C41") (pin "1") (pinfunction "1_1") (pintype "passive"))
      (node (ref "U$9") (pin "P$6") (pinfunction "IN-_P$6") (pintype "bidirectional"))
      (node (ref "U$9") (pin "P$7") (pinfunction "OUT_P$7") (pintype "bidirectional"))
      (node (ref "U4") (pin "$P3") (pinfunction "EC-_$P3") (pintype "bidirectional"))
    )
    (net (code "73") (name "VCA_OUT0") (class "Default")
      (node (ref "C4") (pin "2") (pinfunction "2_2") (pintype "passive"))
      (node (ref "R2") (pin "2") (pinfunction "2_2") (pintype "passive"))
      (node (ref "U$1") (pin "P$1") (pinfunction "OUT_P$1") (pintype "bidirectional"))
    )
    (net (code "74") (name "VCA_OUT1") (class "Default")
      (node (ref "C21") (pin "2") (pinfunction "2_2") (pintype "passive"))
      (node (ref "R9") (pin "2") (pinfunction "2_2") (pintype "passive"))
      (node (ref "U$4") (pin "P$1") (pinfunction "OUT_P$1") (pintype "bidirectional"))
    )
    (net (code "75") (name "VCA_OUT2") (class "Default")
      (node (ref "C29") (pin "2") (pinfunction "2_2") (pintype "passive"))
      (node (ref "R15") (pin "2") (pinfunction "2_2") (pintype "passive"))
      (node (ref "U$5") (pin "P$1") (pinfunction "OUT_P$1") (pintype "bidirectional"))
    )
    (net (code "76") (name "VCA_OUT3") (class "Default")
      (node (ref "C37") (pin "2") (pinfunction "2_2") (pintype "passive"))
      (node (ref "R21") (pin "2") (pinfunction "2_2") (pintype "passive"))
      (node (ref "U$7") (pin "P$1") (pinfunction "OUT_P$1") (pintype "bidirectional"))
    )
    (net (code "77") (name "unconnected-(R37-Pad2)") (class "Default")
      (node (ref "R37") (pin "2") (pinfunction "2_2") (pintype "passive"))
    )
    (net (code "78") (name "unconnected-(R39-Pad2)") (class "Default")
      (node (ref "R39") (pin "2") (pinfunction "2_2") (pintype "passive"))
    )
    (net (code "79") (name "unconnected-(U$2-PA6-PadP$16)") (class "Default")
      (node (ref "U$2") (pin "P$16") (pinfunction "PA6_P$16") (pintype "bidirectional"))
    )
    (net (code "80") (name "unconnected-(U$2-PA12-PadP$33)") (class "Default")
      (node (ref "U$2") (pin "P$33") (pinfunction "PA12_P$33") (pintype "bidirectional"))
    )
    (net (code "81") (name "unconnected-(U$2-PA15-PadP$38)") (class "Default")
      (node (ref "U$2") (pin "P$38") (pinfunction "PA15_P$38") (pintype "bidirectional"))
    )
    (net (code "82") (name "unconnected-(U$2-PB2-PadP$20)") (class "Default")
      (node (ref "U$2") (pin "P$20") (pinfunction "PB2_P$20") (pintype "bidirectional"))
    )
    (net (code "83") (name "unconnected-(U$2-PB6-PadP$42)") (class "Default")
      (node (ref "U$2") (pin "P$42") (pinfunction "PB6_P$42") (pintype "bidirectional"))
    )
    (net (code "84") (name "unconnected-(U$2-PB7-PadP$43)") (class "Default")
      (node (ref "U$2") (pin "P$43") (pinfunction "PB7_P$43") (pintype "bidirectional"))
    )
    (net (code "85") (name "unconnected-(U$2-PB8-PadP$45)") (class "Default")
      (node (ref "U$2") (pin "P$45") (pinfunction "PB8_P$45") (pintype "bidirectional"))
    )
    (net (code "86") (name "unconnected-(U$2-PB9-PadP$46)") (class "Default")
      (node (ref "U$2") (pin "P$46") (pinfunction "PB9_P$46") (pintype "bidirectional"))
    )
    (net (code "87") (name "unconnected-(U$2-PB10-PadP$21)") (class "Default")
      (node (ref "U$2") (pin "P$21") (pinfunction "PB10_P$21") (pintype "bidirectional"))
    )
    (net (code "88") (name "unconnected-(U$2-PB11-PadP$22)") (class "Default")
      (node (ref "U$2") (pin "P$22") (pinfunction "PB11_P$22") (pintype "bidirectional"))
    )
    (net (code "89") (name "unconnected-(U$2-PB12-PadP$25)") (class "Default")
      (node (ref "U$2") (pin "P$25") (pinfunction "PB12_P$25") (pintype "bidirectional"))
    )
    (net (code "90") (name "unconnected-(U$2-PB13-PadP$26)") (class "Default")
      (node (ref "U$2") (pin "P$26") (pinfunction "PB13_P$26") (pintype "bidirectional"))
    )
    (net (code "91") (name "unconnected-(U$2-PB14-PadP$27)") (class "Default")
      (node (ref "U$2") (pin "P$27") (pinfunction "PB14_P$27") (pintype "bidirectional"))
    )
    (net (code "92") (name "unconnected-(U$2-PB15-PadP$28)") (class "Default")
      (node (ref "U$2") (pin "P$28") (pinfunction "PB15_P$28") (pintype "bidirectional"))
    )
    (net (code "93") (name "unconnected-(U$2-PC13-PadP$2)") (class "Default")
      (node (ref "U$2") (pin "P$2") (pinfunction "PC13_P$2") (pintype "bidirectional"))
    )
    (net (code "94") (name "unconnected-(U$2-PC14-OSC32_IN-PadP$3)") (class "Default")
      (node (ref "U$2") (pin "P$3") (pinfunction "PC14-OSC32_IN_P$3") (pintype "bidirectional"))
    )
    (net (code "95") (name "unconnected-(U$2-PC15-OSC32_OUT-PadP$4)") (class "Default")
      (node (ref "U$2") (pin "P$4") (pinfunction "PC15-OSC32_OUT_P$4") (pintype "bidirectional"))
    )
    (net (code "96") (name "unconnected-(U$2-PF0-OSC_IN-PadP$5)") (class "Default")
      (node (ref "U$2") (pin "P$5") (pinfunction "PF0-OSC_IN_P$5") (pintype "bidirectional"))
    )
    (net (code "97") (name "unconnected-(U$2-PF1-OSC_OUT-PadP$6)") (class "Default")
      (node (ref "U$2") (pin "P$6") (pinfunction "PF1-OSC_OUT_P$6") (pintype "bidirectional"))
    )
    (net (code "98") (name "unconnected-(U$2-PF6-PadP$35)") (class "Default")
      (node (ref "U$2") (pin "P$35") (pinfunction "PF6_P$35") (pintype "bidirectional"))
    )
    (net (code "99") (name "unconnected-(U$2-PF7-PadP$36)") (class "Default")
      (node (ref "U$2") (pin "P$36") (pinfunction "PF7_P$36") (pintype "bidirectional"))
    )
    (net (code "100") (name "unconnected-(U$10A-DIODE{slash}BIAS-Pad2)") (class "Default")
      (node (ref "U$10") (pin "2") (pinfunction "DIODE/BIAS_2") (pintype "passive"))
    )
    (net (code "101") (name "unconnected-(U$10B-DIODE{slash}BIAS-Pad15)") (class "Default")
      (node (ref "U$10") (pin "15") (pinfunction "DIODE/BIAS_15") (pintype "passive"))
    )
    (net (code "102") (name "unconnected-(U$11C-V+-PadP$8)") (class "Default")
      (node (ref "U$11") (pin "P$8") (pinfunction "V+_P$8") (pintype "bidirectional"))
    )
    (net (code "103") (name "unconnected-(U$11C-V--PadP$4)") (class "Default")
      (node (ref "U$11") (pin "P$4") (pinfunction "V-_P$4") (pintype "bidirectional"))
    )
    (net (code "104") (name "unconnected-(U1-SYM-Pad$P4)") (class "Default")
      (node (ref "U1") (pin "$P4") (pinfunction "SYM_$P4") (pintype "bidirectional"))
    )
    (net (code "105") (name "unconnected-(U2-SYM-Pad$P4)") (class "Default")
      (node (ref "U2") (pin "$P4") (pinfunction "SYM_$P4") (pintype "bidirectional"))
    )
    (net (code "106") (name "unconnected-(U3-SYM-Pad$P4)") (class "Default")
      (node (ref "U3") (pin "$P4") (pinfunction "SYM_$P4") (pintype "bidirectional"))
    )
    (net (code "107") (name "unconnected-(U4-SYM-Pad$P4)") (class "Default")
      (node (ref "U4") (pin "$P4") (pinfunction "SYM_$P4") (pintype "bidirectional"))
    )
  )
)
